# Sheet1.net
KiCad netlist of a schematic drawn in Altium Designer
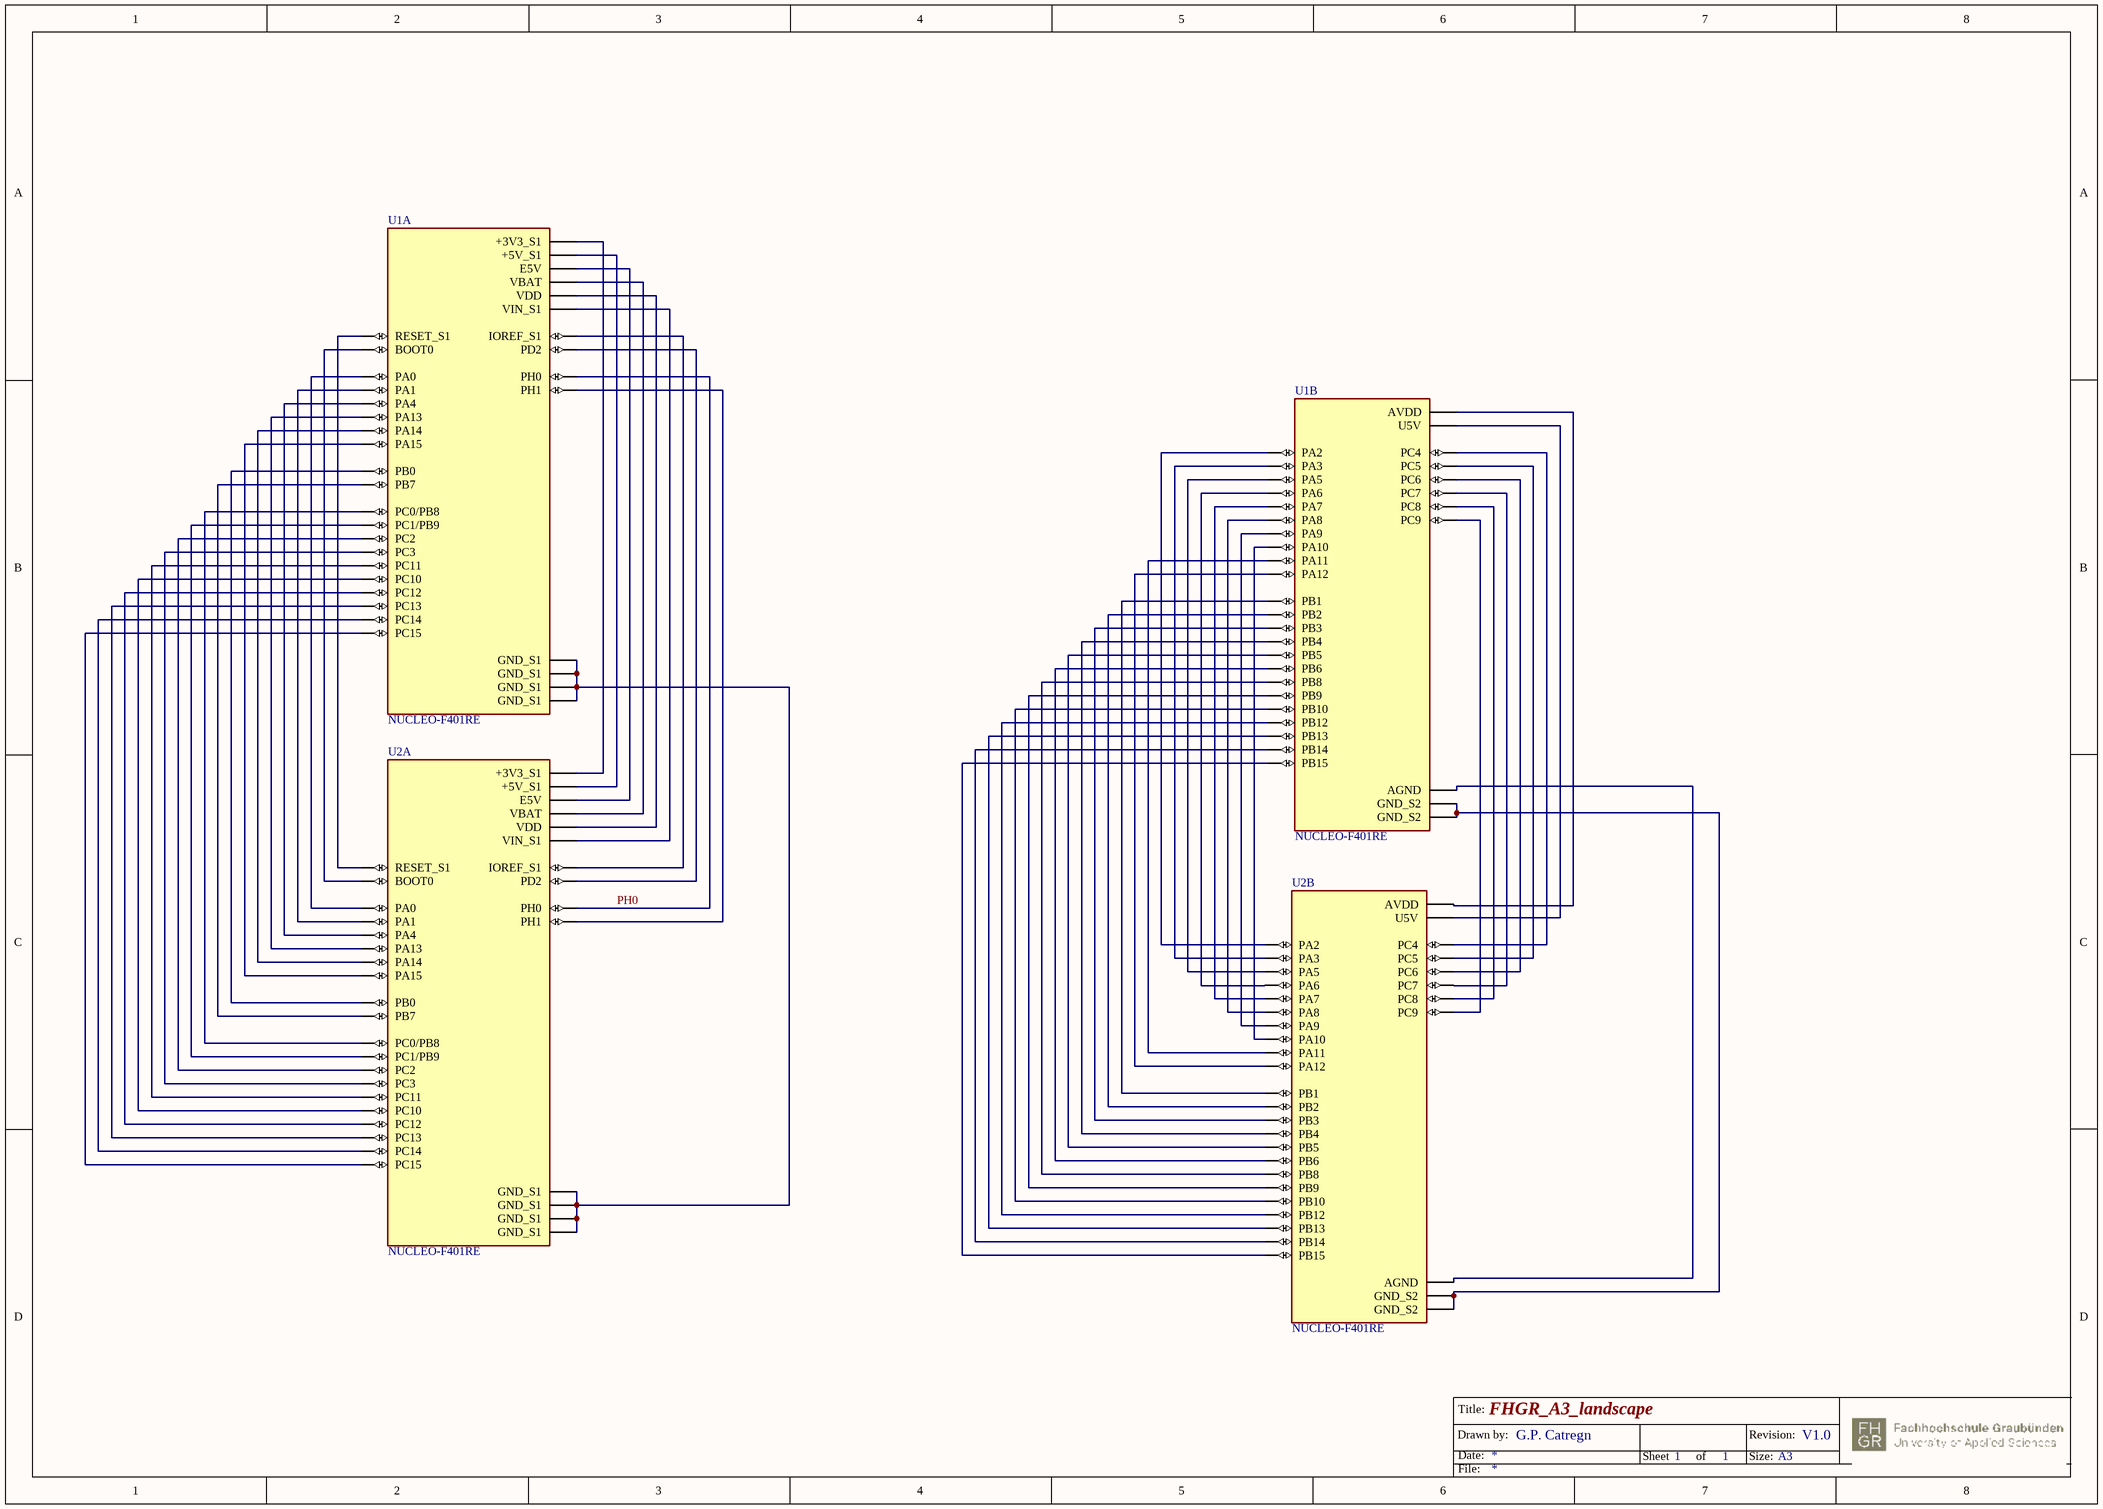
[diagram p0: Sheet1.SchDoc]

(export (version "E")
  (design (tool "Eeschema 10.0.6"))
  (components
    (comp (ref "U1")
      (value "NUCLEO-F401RE")
      (footprint "ST_NUCLEO-F401RE")
      (libsource (lib "NUCLEO-F401RE") (part "NUCLEO-F401RE"))
    )
    (comp (ref "U2")
      (value "NUCLEO-F401RE")
      (footprint "ST_NUCLEO-F401RE")
      (libsource (lib "NUCLEO-F401RE") (part "NUCLEO-F401RE"))
    )
  )
  (nets
    (net (code "1") (name "/PH0") (class "Default")
      (node (ref "U1") (pin "CN7_29") (pinfunction "PH0_CN7_29") (pintype "bidirectional"))
      (node (ref "U2") (pin "CN7_29") (pinfunction "PH0_CN7_29") (pintype "bidirectional"))
    )
    (net (code "2") (name "Net-(U1A-+3V3_S1)") (class "Default")
      (node (ref "U1") (pin "CN7_16") (pinfunction "+3V3_S1_CN7_16") (pintype "power_in"))
      (node (ref "U2") (pin "CN7_16") (pinfunction "+3V3_S1_CN7_16") (pintype "power_in"))
    )
    (net (code "3") (name "Net-(U1A-+5V_S1)") (class "Default")
      (node (ref "U1") (pin "CN7_18") (pinfunction "+5V_S1_CN7_18") (pintype "power_in"))
      (node (ref "U2") (pin "CN7_18") (pinfunction "+5V_S1_CN7_18") (pintype "power_in"))
    )
    (net (code "4") (name "Net-(U1A-BOOT0)") (class "Default")
      (node (ref "U1") (pin "CN7_7") (pinfunction "BOOT0_CN7_7") (pintype "bidirectional"))
      (node (ref "U2") (pin "CN7_7") (pinfunction "BOOT0_CN7_7") (pintype "bidirectional"))
    )
    (net (code "5") (name "Net-(U1A-E5V)") (class "Default")
      (node (ref "U1") (pin "CN7_6") (pinfunction "E5V_CN7_6") (pintype "power_in"))
      (node (ref "U2") (pin "CN7_6") (pinfunction "E5V_CN7_6") (pintype "power_in"))
    )
    (net (code "6") (name "Net-(U1A-GND_S1-PadCN7_19)") (class "Default")
      (node (ref "U1") (pin "CN7_19") (pinfunction "GND_S1_CN7_19") (pintype "power_in"))
      (node (ref "U1") (pin "CN7_20") (pinfunction "GND_S1_CN7_20") (pintype "power_in"))
      (node (ref "U1") (pin "CN7_22") (pinfunction "GND_S1_CN7_22") (pintype "power_in"))
      (node (ref "U1") (pin "CN7_8") (pinfunction "GND_S1_CN7_8") (pintype "power_in"))
      (node (ref "U2") (pin "CN7_19") (pinfunction "GND_S1_CN7_19") (pintype "power_in"))
      (node (ref "U2") (pin "CN7_20") (pinfunction "GND_S1_CN7_20") (pintype "power_in"))
      (node (ref "U2") (pin "CN7_22") (pinfunction "GND_S1_CN7_22") (pintype "power_in"))
      (node (ref "U2") (pin "CN7_8") (pinfunction "GND_S1_CN7_8") (pintype "power_in"))
    )
    (net (code "7") (name "Net-(U1A-IOREF_S1)") (class "Default")
      (node (ref "U1") (pin "CN7_12") (pinfunction "IOREF_S1_CN7_12") (pintype "bidirectional"))
      (node (ref "U2") (pin "CN7_12") (pinfunction "IOREF_S1_CN7_12") (pintype "bidirectional"))
    )
    (net (code "8") (name "Net-(U1A-PA0)") (class "Default")
      (node (ref "U1") (pin "CN7_28") (pinfunction "PA0_CN7_28") (pintype "bidirectional"))
      (node (ref "U2") (pin "CN7_28") (pinfunction "PA0_CN7_28") (pintype "bidirectional"))
    )
    (net (code "9") (name "Net-(U1A-PA1)") (class "Default")
      (node (ref "U1") (pin "CN7_30") (pinfunction "PA1_CN7_30") (pintype "bidirectional"))
      (node (ref "U2") (pin "CN7_30") (pinfunction "PA1_CN7_30") (pintype "bidirectional"))
    )
    (net (code "10") (name "Net-(U1A-PA4)") (class "Default")
      (node (ref "U1") (pin "CN7_32") (pinfunction "PA4_CN7_32") (pintype "bidirectional"))
      (node (ref "U2") (pin "CN7_32") (pinfunction "PA4_CN7_32") (pintype "bidirectional"))
    )
    (net (code "11") (name "Net-(U1A-PA13)") (class "Default")
      (node (ref "U1") (pin "CN7_13") (pinfunction "PA13_CN7_13") (pintype "bidirectional"))
      (node (ref "U2") (pin "CN7_13") (pinfunction "PA13_CN7_13") (pintype "bidirectional"))
    )
    (net (code "12") (name "Net-(U1A-PA14)") (class "Default")
      (node (ref "U1") (pin "CN7_15") (pinfunction "PA14_CN7_15") (pintype "bidirectional"))
      (node (ref "U2") (pin "CN7_15") (pinfunction "PA14_CN7_15") (pintype "bidirectional"))
    )
    (net (code "13") (name "Net-(U1A-PA15)") (class "Default")
      (node (ref "U1") (pin "CN7_17") (pinfunction "PA15_CN7_17") (pintype "bidirectional"))
      (node (ref "U2") (pin "CN7_17") (pinfunction "PA15_CN7_17") (pintype "bidirectional"))
    )
    (net (code "14") (name "Net-(U1A-PB0)") (class "Default")
      (node (ref "U1") (pin "CN7_34") (pinfunction "PB0_CN7_34") (pintype "bidirectional"))
      (node (ref "U2") (pin "CN7_34") (pinfunction "PB0_CN7_34") (pintype "bidirectional"))
    )
    (net (code "15") (name "Net-(U1A-PB7)") (class "Default")
      (node (ref "U1") (pin "CN7_21") (pinfunction "PB7_CN7_21") (pintype "bidirectional"))
      (node (ref "U2") (pin "CN7_21") (pinfunction "PB7_CN7_21") (pintype "bidirectional"))
    )
    (net (code "16") (name "Net-(U1A-PC0{slash}PB8)") (class "Default")
      (node (ref "U1") (pin "CN7_38") (pinfunction "PC0/PB8_CN7_38") (pintype "bidirectional"))
      (node (ref "U2") (pin "CN7_38") (pinfunction "PC0/PB8_CN7_38") (pintype "bidirectional"))
    )
    (net (code "17") (name "Net-(U1A-PC1{slash}PB9)") (class "Default")
      (node (ref "U1") (pin "CN7_36") (pinfunction "PC1/PB9_CN7_36") (pintype "bidirectional"))
      (node (ref "U2") (pin "CN7_36") (pinfunction "PC1/PB9_CN7_36") (pintype "bidirectional"))
    )
    (net (code "18") (name "Net-(U1A-PC2)") (class "Default")
      (node (ref "U1") (pin "CN7_35") (pinfunction "PC2_CN7_35") (pintype "bidirectional"))
      (node (ref "U2") (pin "CN7_35") (pinfunction "PC2_CN7_35") (pintype "bidirectional"))
    )
    (net (code "19") (name "Net-(U1A-PC3)") (class "Default")
      (node (ref "U1") (pin "CN7_37") (pinfunction "PC3_CN7_37") (pintype "bidirectional"))
      (node (ref "U2") (pin "CN7_37") (pinfunction "PC3_CN7_37") (pintype "bidirectional"))
    )
    (net (code "20") (name "Net-(U1A-PC10)") (class "Default")
      (node (ref "U1") (pin "CN7_1") (pinfunction "PC10_CN7_1") (pintype "bidirectional"))
      (node (ref "U2") (pin "CN7_1") (pinfunction "PC10_CN7_1") (pintype "bidirectional"))
    )
    (net (code "21") (name "Net-(U1A-PC11)") (class "Default")
      (node (ref "U1") (pin "CN7_2") (pinfunction "PC11_CN7_2") (pintype "bidirectional"))
      (node (ref "U2") (pin "CN7_2") (pinfunction "PC11_CN7_2") (pintype "bidirectional"))
    )
    (net (code "22") (name "Net-(U1A-PC12)") (class "Default")
      (node (ref "U1") (pin "CN7_3") (pinfunction "PC12_CN7_3") (pintype "bidirectional"))
      (node (ref "U2") (pin "CN7_3") (pinfunction "PC12_CN7_3") (pintype "bidirectional"))
    )
    (net (code "23") (name "Net-(U1A-PC13)") (class "Default")
      (node (ref "U1") (pin "CN7_23") (pinfunction "PC13_CN7_23") (pintype "bidirectional"))
      (node (ref "U2") (pin "CN7_23") (pinfunction "PC13_CN7_23") (pintype "bidirectional"))
    )
    (net (code "24") (name "Net-(U1A-PC14)") (class "Default")
      (node (ref "U1") (pin "CN7_25") (pinfunction "PC14_CN7_25") (pintype "bidirectional"))
      (node (ref "U2") (pin "CN7_25") (pinfunction "PC14_CN7_25") (pintype "bidirectional"))
    )
    (net (code "25") (name "Net-(U1A-PC15)") (class "Default")
      (node (ref "U1") (pin "CN7_27") (pinfunction "PC15_CN7_27") (pintype "bidirectional"))
      (node (ref "U2") (pin "CN7_27") (pinfunction "PC15_CN7_27") (pintype "bidirectional"))
    )
    (net (code "26") (name "Net-(U1A-PD2)") (class "Default")
      (node (ref "U1") (pin "CN7_4") (pinfunction "PD2_CN7_4") (pintype "bidirectional"))
      (node (ref "U2") (pin "CN7_4") (pinfunction "PD2_CN7_4") (pintype "bidirectional"))
    )
    (net (code "27") (name "Net-(U1A-PH1)") (class "Default")
      (node (ref "U1") (pin "CN7_31") (pinfunction "PH1_CN7_31") (pintype "bidirectional"))
      (node (ref "U2") (pin "CN7_31") (pinfunction "PH1_CN7_31") (pintype "bidirectional"))
    )
    (net (code "28") (name "Net-(U1A-RESET_S1)") (class "Default")
      (node (ref "U1") (pin "CN7_14") (pinfunction "RESET_S1_CN7_14") (pintype "bidirectional"))
      (node (ref "U2") (pin "CN7_14") (pinfunction "RESET_S1_CN7_14") (pintype "bidirectional"))
    )
    (net (code "29") (name "Net-(U1A-VBAT)") (class "Default")
      (node (ref "U1") (pin "CN7_33") (pinfunction "VBAT_CN7_33") (pintype "power_in"))
      (node (ref "U2") (pin "CN7_33") (pinfunction "VBAT_CN7_33") (pintype "power_in"))
    )
    (net (code "30") (name "Net-(U1A-VDD)") (class "Default")
      (node (ref "U1") (pin "CN7_5") (pinfunction "VDD_CN7_5") (pintype "power_in"))
      (node (ref "U2") (pin "CN7_5") (pinfunction "VDD_CN7_5") (pintype "power_in"))
    )
    (net (code "31") (name "Net-(U1A-VIN_S1)") (class "Default")
      (node (ref "U1") (pin "CN7_24") (pinfunction "VIN_S1_CN7_24") (pintype "power_in"))
      (node (ref "U2") (pin "CN7_24") (pinfunction "VIN_S1_CN7_24") (pintype "power_in"))
    )
    (net (code "32") (name "Net-(U1B-AGND)") (class "Default")
      (node (ref "U1") (pin "CN10_32") (pinfunction "AGND_CN10_32") (pintype "power_in"))
      (node (ref "U2") (pin "CN10_32") (pinfunction "AGND_CN10_32") (pintype "power_in"))
    )
    (net (code "33") (name "Net-(U1B-AVDD)") (class "Default")
      (node (ref "U1") (pin "CN10_7") (pinfunction "AVDD_CN10_7") (pintype "power_in"))
      (node (ref "U2") (pin "CN10_7") (pinfunction "AVDD_CN10_7") (pintype "power_in"))
    )
    (net (code "34") (name "Net-(U1B-GND_S2-PadCN10_20)") (class "Default")
      (node (ref "U1") (pin "CN10_20") (pinfunction "GND_S2_CN10_20") (pintype "power_in"))
      (node (ref "U1") (pin "CN10_9") (pinfunction "GND_S2_CN10_9") (pintype "power_in"))
      (node (ref "U2") (pin "CN10_20") (pinfunction "GND_S2_CN10_20") (pintype "power_in"))
      (node (ref "U2") (pin "CN10_9") (pinfunction "GND_S2_CN10_9") (pintype "power_in"))
    )
    (net (code "35") (name "Net-(U1B-PA2)") (class "Default")
      (node (ref "U1") (pin "CN10_35") (pinfunction "PA2_CN10_35") (pintype "bidirectional"))
      (node (ref "U2") (pin "CN10_35") (pinfunction "PA2_CN10_35") (pintype "bidirectional"))
    )
    (net (code "36") (name "Net-(U1B-PA3)") (class "Default")
      (node (ref "U1") (pin "CN10_37") (pinfunction "PA3_CN10_37") (pintype "bidirectional"))
      (node (ref "U2") (pin "CN10_37") (pinfunction "PA3_CN10_37") (pintype "bidirectional"))
    )
    (net (code "37") (name "Net-(U1B-PA5)") (class "Default")
      (node (ref "U1") (pin "CN10_11") (pinfunction "PA5_CN10_11") (pintype "bidirectional"))
      (node (ref "U2") (pin "CN10_11") (pinfunction "PA5_CN10_11") (pintype "bidirectional"))
    )
    (net (code "38") (name "Net-(U1B-PA6)") (class "Default")
      (node (ref "U1") (pin "CN10_13") (pinfunction "PA6_CN10_13") (pintype "bidirectional"))
      (node (ref "U2") (pin "CN10_13") (pinfunction "PA6_CN10_13") (pintype "bidirectional"))
    )
    (net (code "39") (name "Net-(U1B-PA7)") (class "Default")
      (node (ref "U1") (pin "CN10_15") (pinfunction "PA7_CN10_15") (pintype "bidirectional"))
      (node (ref "U2") (pin "CN10_15") (pinfunction "PA7_CN10_15") (pintype "bidirectional"))
    )
    (net (code "40") (name "Net-(U1B-PA8)") (class "Default")
      (node (ref "U1") (pin "CN10_23") (pinfunction "PA8_CN10_23") (pintype "bidirectional"))
      (node (ref "U2") (pin "CN10_23") (pinfunction "PA8_CN10_23") (pintype "bidirectional"))
    )
    (net (code "41") (name "Net-(U1B-PA9)") (class "Default")
      (node (ref "U1") (pin "CN10_21") (pinfunction "PA9_CN10_21") (pintype "bidirectional"))
      (node (ref "U2") (pin "CN10_21") (pinfunction "PA9_CN10_21") (pintype "bidirectional"))
    )
    (net (code "42") (name "Net-(U1B-PA10)") (class "Default")
      (node (ref "U1") (pin "CN10_33") (pinfunction "PA10_CN10_33") (pintype "bidirectional"))
      (node (ref "U2") (pin "CN10_33") (pinfunction "PA10_CN10_33") (pintype "bidirectional"))
    )
    (net (code "43") (name "Net-(U1B-PA11)") (class "Default")
      (node (ref "U1") (pin "CN10_14") (pinfunction "PA11_CN10_14") (pintype "bidirectional"))
      (node (ref "U2") (pin "CN10_14") (pinfunction "PA11_CN10_14") (pintype "bidirectional"))
    )
    (net (code "44") (name "Net-(U1B-PA12)") (class "Default")
      (node (ref "U1") (pin "CN10_12") (pinfunction "PA12_CN10_12") (pintype "bidirectional"))
      (node (ref "U2") (pin "CN10_12") (pinfunction "PA12_CN10_12") (pintype "bidirectional"))
    )
    (net (code "45") (name "Net-(U1B-PB1)") (class "Default")
      (node (ref "U1") (pin "CN10_24") (pinfunction "PB1_CN10_24") (pintype "bidirectional"))
      (node (ref "U2") (pin "CN10_24") (pinfunction "PB1_CN10_24") (pintype "bidirectional"))
    )
    (net (code "46") (name "Net-(U1B-PB2)") (class "Default")
      (node (ref "U1") (pin "CN10_22") (pinfunction "PB2_CN10_22") (pintype "bidirectional"))
      (node (ref "U2") (pin "CN10_22") (pinfunction "PB2_CN10_22") (pintype "bidirectional"))
    )
    (net (code "47") (name "Net-(U1B-PB3)") (class "Default")
      (node (ref "U1") (pin "CN10_31") (pinfunction "PB3_CN10_31") (pintype "bidirectional"))
      (node (ref "U2") (pin "CN10_31") (pinfunction "PB3_CN10_31") (pintype "bidirectional"))
    )
    (net (code "48") (name "Net-(U1B-PB4)") (class "Default")
      (node (ref "U1") (pin "CN10_27") (pinfunction "PB4_CN10_27") (pintype "bidirectional"))
      (node (ref "U2") (pin "CN10_27") (pinfunction "PB4_CN10_27") (pintype "bidirectional"))
    )
    (net (code "49") (name "Net-(U1B-PB5)") (class "Default")
      (node (ref "U1") (pin "CN10_29") (pinfunction "PB5_CN10_29") (pintype "bidirectional"))
      (node (ref "U2") (pin "CN10_29") (pinfunction "PB5_CN10_29") (pintype "bidirectional"))
    )
    (net (code "50") (name "Net-(U1B-PB6)") (class "Default")
      (node (ref "U1") (pin "CN10_17") (pinfunction "PB6_CN10_17") (pintype "bidirectional"))
      (node (ref "U2") (pin "CN10_17") (pinfunction "PB6_CN10_17") (pintype "bidirectional"))
    )
    (net (code "51") (name "Net-(U1B-PB8)") (class "Default")
      (node (ref "U1") (pin "CN10_3") (pinfunction "PB8_CN10_3") (pintype "bidirectional"))
      (node (ref "U2") (pin "CN10_3") (pinfunction "PB8_CN10_3") (pintype "bidirectional"))
    )
    (net (code "52") (name "Net-(U1B-PB9)") (class "Default")
      (node (ref "U1") (pin "CN10_5") (pinfunction "PB9_CN10_5") (pintype "bidirectional"))
      (node (ref "U2") (pin "CN10_5") (pinfunction "PB9_CN10_5") (pintype "bidirectional"))
    )
    (net (code "53") (name "Net-(U1B-PB10)") (class "Default")
      (node (ref "U1") (pin "CN10_25") (pinfunction "PB10_CN10_25") (pintype "bidirectional"))
      (node (ref "U2") (pin "CN10_25") (pinfunction "PB10_CN10_25") (pintype "bidirectional"))
    )
    (net (code "54") (name "Net-(U1B-PB12)") (class "Default")
      (node (ref "U1") (pin "CN10_16") (pinfunction "PB12_CN10_16") (pintype "bidirectional"))
      (node (ref "U2") (pin "CN10_16") (pinfunction "PB12_CN10_16") (pintype "bidirectional"))
    )
    (net (code "55") (name "Net-(U1B-PB13)") (class "Default")
      (node (ref "U1") (pin "CN10_30") (pinfunction "PB13_CN10_30") (pintype "bidirectional"))
      (node (ref "U2") (pin "CN10_30") (pinfunction "PB13_CN10_30") (pintype "bidirectional"))
    )
    (net (code "56") (name "Net-(U1B-PB14)") (class "Default")
      (node (ref "U1") (pin "CN10_28") (pinfunction "PB14_CN10_28") (pintype "bidirectional"))
      (node (ref "U2") (pin "CN10_28") (pinfunction "PB14_CN10_28") (pintype "bidirectional"))
    )
    (net (code "57") (name "Net-(U1B-PB15)") (class "Default")
      (node (ref "U1") (pin "CN10_26") (pinfunction "PB15_CN10_26") (pintype "bidirectional"))
      (node (ref "U2") (pin "CN10_26") (pinfunction "PB15_CN10_26") (pintype "bidirectional"))
    )
    (net (code "58") (name "Net-(U1B-PC4)") (class "Default")
      (node (ref "U1") (pin "CN10_34") (pinfunction "PC4_CN10_34") (pintype "bidirectional"))
      (node (ref "U2") (pin "CN10_34") (pinfunction "PC4_CN10_34") (pintype "bidirectional"))
    )
    (net (code "59") (name "Net-(U1B-PC5)") (class "Default")
      (node (ref "U1") (pin "CN10_6") (pinfunction "PC5_CN10_6") (pintype "bidirectional"))
      (node (ref "U2") (pin "CN10_6") (pinfunction "PC5_CN10_6") (pintype "bidirectional"))
    )
    (net (code "60") (name "Net-(U1B-PC6)") (class "Default")
      (node (ref "U1") (pin "CN10_4") (pinfunction "PC6_CN10_4") (pintype "bidirectional"))
      (node (ref "U2") (pin "CN10_4") (pinfunction "PC6_CN10_4") (pintype "bidirectional"))
    )
    (net (code "61") (name "Net-(U1B-PC7)") (class "Default")
      (node (ref "U1") (pin "CN10_19") (pinfunction "PC7_CN10_19") (pintype "bidirectional"))
      (node (ref "U2") (pin "CN10_19") (pinfunction "PC7_CN10_19") (pintype "bidirectional"))
    )
    (net (code "62") (name "Net-(U1B-PC8)") (class "Default")
      (node (ref "U1") (pin "CN10_2") (pinfunction "PC8_CN10_2") (pintype "bidirectional"))
      (node (ref "U2") (pin "CN10_2") (pinfunction "PC8_CN10_2") (pintype "bidirectional"))
    )
    (net (code "63") (name "Net-(U1B-PC9)") (class "Default")
      (node (ref "U1") (pin "CN10_1") (pinfunction "PC9_CN10_1") (pintype "bidirectional"))
      (node (ref "U2") (pin "CN10_1") (pinfunction "PC9_CN10_1") (pintype "bidirectional"))
    )
    (net (code "64") (name "Net-(U1B-U5V)") (class "Default")
      (node (ref "U1") (pin "CN10_8") (pinfunction "U5V_CN10_8") (pintype "power_in"))
      (node (ref "U2") (pin "CN10_8") (pinfunction "U5V_CN10_8") (pintype "power_in"))
    )
  )
)
